# SCH_business-card_2024-06-19.net
KiCad netlist of a schematic drawn in EasyEDA
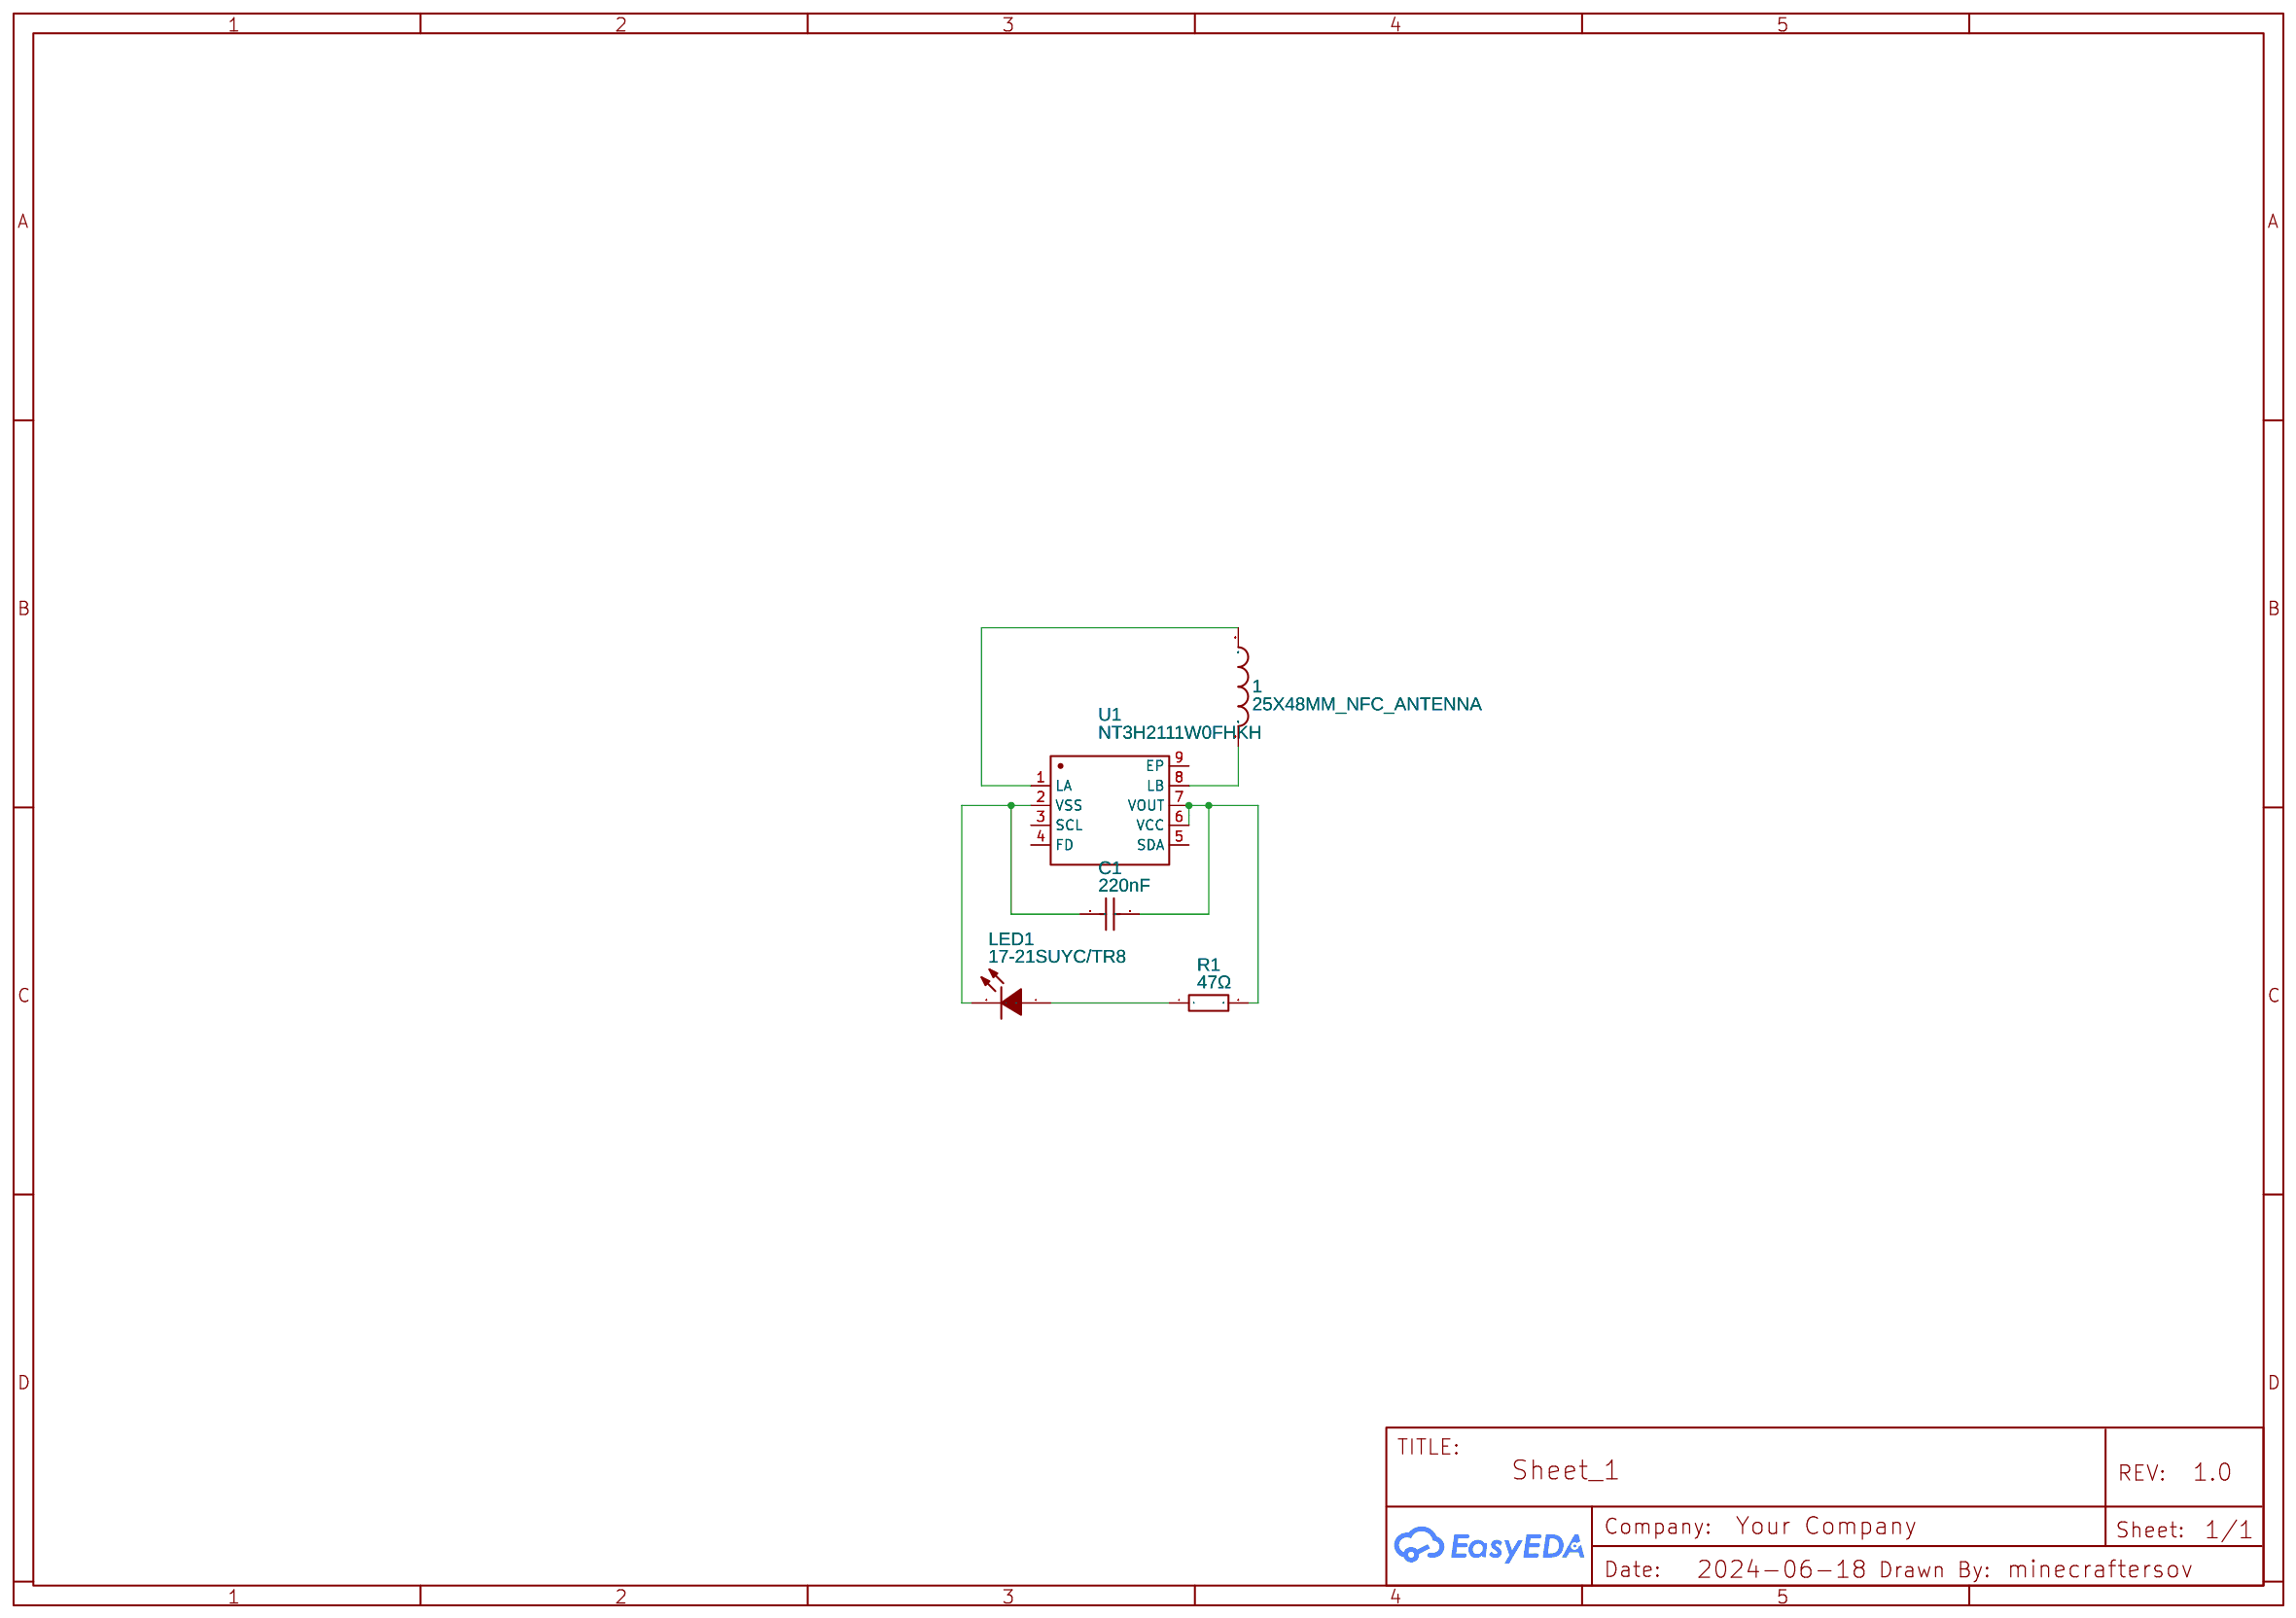
[diagram p0: schematic sheet]

(export (version "E")
  (design (tool "Eeschema 10.0.6"))
  (components
    (comp (ref "1") (value "25X48MM_NFC_ANTENNA") (libsource (lib "") (part "25X48MM_NFC_ANTENNA")))
    (comp (ref "C1")
      (value "220nF")
      (fields
        (field (name "Manufacturer Part") "CL10B224KA8NNNC")
        (field (name "Manufacturer") "SAMSUNG(三星)")
      )
      (libsource (lib "") (part "CL10B224KA8NNNC"))
    )
    (comp (ref "LED1")
      (value "17-21SUYC/TR8")
      (fields (field (name "Manufacturer Part") "KT-0805黄灯") (field (name "Manufacturer") "KENTO"))
      (libsource (lib "") (part "17-21SUYC/TR8"))
    )
    (comp (ref "R1")
      (value "47Ω")
      (fields
        (field (name "Manufacturer Part") "0603WAF470JT5E")
        (field (name "Manufacturer") "UNI-ROYAL(厚声)")
      )
      (libsource (lib "") (part "0603WAF470JT5E"))
    )
    (comp (ref "U1")
      (value "NT3H2111W0FHKH")
      (fields (field (name "Manufacturer") "NXP(恩智浦)"))
      (libsource (lib "") (part "NT3H2111W0FHKH"))
    )
  )
  (nets
    (net (code "1") (name "Net-(LED1-+)") (class "Default")
      (node (ref "LED1") (pin "1") (pinfunction "+_1") (pintype "unspecified"))
      (node (ref "R1") (pin "1") (pinfunction "1_1") (pintype "input"))
    )
    (net (code "2") (name "Net-(LED1--)") (class "Default")
      (node (ref "C1") (pin "1") (pinfunction "1_1") (pintype "input"))
      (node (ref "LED1") (pin "2") (pinfunction "-_2") (pintype "unspecified"))
      (node (ref "U1") (pin "2") (pinfunction "VSS_2") (pintype "unspecified"))
    )
    (net (code "3") (name "Net-(U1-LA)") (class "Default")
      (node (ref "1") (pin "P$1") (pinfunction "P$1_P$1") (pintype "bidirectional"))
      (node (ref "U1") (pin "1") (pinfunction "LA_1") (pintype "unspecified"))
    )
    (net (code "4") (name "Net-(U1-LB)") (class "Default")
      (node (ref "1") (pin "P$2") (pinfunction "P$2_P$2") (pintype "bidirectional"))
      (node (ref "U1") (pin "8") (pinfunction "LB_8") (pintype "unspecified"))
    )
    (net (code "5") (name "Net-(U1-VCC)") (class "Default")
      (node (ref "C1") (pin "2") (pinfunction "2_2") (pintype "input"))
      (node (ref "R1") (pin "2") (pinfunction "2_2") (pintype "input"))
      (node (ref "U1") (pin "6") (pinfunction "VCC_6") (pintype "unspecified"))
      (node (ref "U1") (pin "7") (pinfunction "VOUT_7") (pintype "unspecified"))
    )
    (net (code "6") (name "unconnected-(U1-EP-Pad9)") (class "Default")
      (node (ref "U1") (pin "9") (pinfunction "EP_9") (pintype "unspecified"))
    )
    (net (code "7") (name "unconnected-(U1-FD-Pad4)") (class "Default")
      (node (ref "U1") (pin "4") (pinfunction "FD_4") (pintype "unspecified"))
    )
    (net (code "8") (name "unconnected-(U1-SCL-Pad3)") (class "Default")
      (node (ref "U1") (pin "3") (pinfunction "SCL_3") (pintype "unspecified"))
    )
    (net (code "9") (name "unconnected-(U1-SDA-Pad5)") (class "Default")
      (node (ref "U1") (pin "5") (pinfunction "SDA_5") (pintype "unspecified"))
    )
  )
)
